# 05-LED-RED.net
KiCad netlist of a schematic drawn in Altium Designer
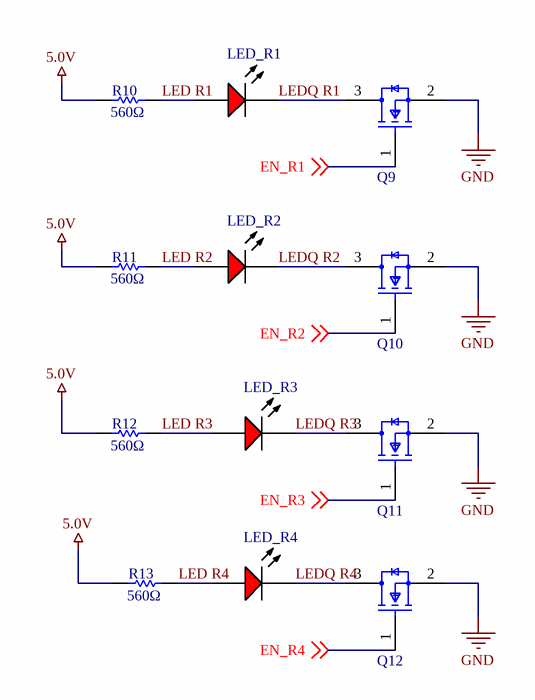
[diagram p0: 05-LED-RED.SchDoc]

(export (version "E")
  (design (tool "Eeschema 10.0.6"))
  (components
    (comp (ref "LED_R1")
      (value "SML-LX1206IC-TR")
      (footprint "LUMX-SML-LX1206IC_V")
      (description "LED Red, 65 mW, -40 to 85 degC, 2-Pin SMD, RoHS, Tape and Reel")
      (fields (field (name "MANUFACTURER") "Lumex"))
      (libsource (lib "Altium Content Vault") (part "LED-RED-AK-2"))
    )
    (comp (ref "LED_R2")
      (value "SML-LX1206IC-TR")
      (footprint "LUMX-SML-LX1206IC_V")
      (description "LED Red, 65 mW, -40 to 85 degC, 2-Pin SMD, RoHS, Tape and Reel")
      (fields (field (name "MANUFACTURER") "Lumex"))
      (libsource (lib "Altium Content Vault") (part "LED-RED-AK-2"))
    )
    (comp (ref "LED_R3")
      (value "SML-LX1206IC-TR")
      (footprint "LUMX-SML-LX1206IC_V")
      (description "LED Red, 65 mW, -40 to 85 degC, 2-Pin SMD, RoHS, Tape and Reel")
      (fields (field (name "MANUFACTURER") "Lumex"))
      (libsource (lib "Altium Content Vault") (part "LED-RED-AK-2"))
    )
    (comp (ref "LED_R4")
      (value "SML-LX1206IC-TR")
      (footprint "LUMX-SML-LX1206IC_V")
      (description "LED Red, 65 mW, -40 to 85 degC, 2-Pin SMD, RoHS, Tape and Reel")
      (fields (field (name "MANUFACTURER") "Lumex"))
      (libsource (lib "Altium Content Vault") (part "LED-RED-AK-2"))
    )
    (comp (ref "Q9")
      (value "2N7002-7-F")
      (footprint "FP-SOT23-MFG")
      (description "MOSFET N-CH 60V 115MA SOT23-3")
      (fields (field (name "VOLTAGE") "60V"))
      (libsource (lib "Altium Content Vault") (part "3b9c635fedb024a5347a57b145af9cc"))
    )
    (comp (ref "Q10")
      (value "2N7002-7-F")
      (footprint "FP-SOT23-MFG")
      (description "MOSFET N-CH 60V 115MA SOT23-3")
      (fields (field (name "VOLTAGE") "60V"))
      (libsource (lib "Altium Content Vault") (part "3b9c635fedb024a5347a57b145af9cc"))
    )
    (comp (ref "Q11")
      (value "2N7002-7-F")
      (footprint "FP-SOT23-MFG")
      (description "MOSFET N-CH 60V 115MA SOT23-3")
      (fields (field (name "VOLTAGE") "60V"))
      (libsource (lib "Altium Content Vault") (part "3b9c635fedb024a5347a57b145af9cc"))
    )
    (comp (ref "Q12")
      (value "2N7002-7-F")
      (footprint "FP-SOT23-MFG")
      (description "MOSFET N-CH 60V 115MA SOT23-3")
      (fields (field (name "VOLTAGE") "60V"))
      (libsource (lib "Altium Content Vault") (part "3b9c635fedb024a5347a57b145af9cc"))
    )
    (comp (ref "R10")
      (value "560Ω")
      (footprint "RESC3216X70X50LL05T20")
      (fields (field (name "PART NUMBER") "ERJ8ENF5600V") (field (name "MANUFACTURER") "Panasonic"))
      (libsource (lib "Altium Content Vault") (part "RES"))
    )
    (comp (ref "R11")
      (value "560Ω")
      (footprint "RESC3216X70X50LL05T20")
      (fields (field (name "PART NUMBER") "ERJ8ENF5600V") (field (name "MANUFACTURER") "Panasonic"))
      (libsource (lib "Altium Content Vault") (part "RES"))
    )
    (comp (ref "R12")
      (value "560Ω")
      (footprint "RESC3216X70X50LL05T20")
      (fields (field (name "PART NUMBER") "ERJ8ENF5600V") (field (name "MANUFACTURER") "Panasonic"))
      (libsource (lib "Altium Content Vault") (part "RES"))
    )
    (comp (ref "R13")
      (value "560Ω")
      (footprint "RESC3216X70X50LL05T20")
      (fields (field (name "PART NUMBER") "ERJ8ENF5600V") (field (name "MANUFACTURER") "Panasonic"))
      (libsource (lib "Altium Content Vault") (part "RES"))
    )
  )
  (nets
    (net (code "1") (name "/LED R1") (class "Default")
      (node (ref "LED_R1") (pin "1") (pinfunction "A_1") (pintype "passive"))
      (node (ref "R10") (pin "2") (pinfunction "2_2") (pintype "passive"))
    )
    (net (code "2") (name "/LED R2") (class "Default")
      (node (ref "LED_R2") (pin "1") (pinfunction "A_1") (pintype "passive"))
      (node (ref "R11") (pin "2") (pinfunction "2_2") (pintype "passive"))
    )
    (net (code "3") (name "/LED R3") (class "Default")
      (node (ref "LED_R3") (pin "1") (pinfunction "A_1") (pintype "passive"))
      (node (ref "R12") (pin "2") (pinfunction "2_2") (pintype "passive"))
    )
    (net (code "4") (name "/LED R4") (class "Default")
      (node (ref "LED_R4") (pin "1") (pinfunction "A_1") (pintype "passive"))
      (node (ref "R13") (pin "2") (pinfunction "2_2") (pintype "passive"))
    )
    (net (code "5") (name "/LEDQ R1") (class "Default")
      (node (ref "LED_R1") (pin "2") (pinfunction "K_2") (pintype "passive"))
      (node (ref "Q9") (pin "3") (pinfunction "D_3") (pintype "passive"))
    )
    (net (code "6") (name "/LEDQ R2") (class "Default")
      (node (ref "LED_R2") (pin "2") (pinfunction "K_2") (pintype "passive"))
      (node (ref "Q10") (pin "3") (pinfunction "D_3") (pintype "passive"))
    )
    (net (code "7") (name "/LEDQ R3") (class "Default")
      (node (ref "LED_R3") (pin "2") (pinfunction "K_2") (pintype "passive"))
      (node (ref "Q11") (pin "3") (pinfunction "D_3") (pintype "passive"))
    )
    (net (code "8") (name "/LEDQ R4") (class "Default")
      (node (ref "LED_R4") (pin "2") (pinfunction "K_2") (pintype "passive"))
      (node (ref "Q12") (pin "3") (pinfunction "D_3") (pintype "passive"))
    )
    (net (code "9") (name "5.0V") (class "Default")
      (node (ref "R10") (pin "1") (pinfunction "1_1") (pintype "passive"))
      (node (ref "R11") (pin "1") (pinfunction "1_1") (pintype "passive"))
      (node (ref "R12") (pin "1") (pinfunction "1_1") (pintype "passive"))
      (node (ref "R13") (pin "1") (pinfunction "1_1") (pintype "passive"))
    )
    (net (code "10") (name "EN_R1") (class "Default")
      (node (ref "Q9") (pin "1") (pinfunction "G_1") (pintype "passive"))
    )
    (net (code "11") (name "EN_R2") (class "Default")
      (node (ref "Q10") (pin "1") (pinfunction "G_1") (pintype "passive"))
    )
    (net (code "12") (name "EN_R3") (class "Default")
      (node (ref "Q11") (pin "1") (pinfunction "G_1") (pintype "passive"))
    )
    (net (code "13") (name "EN_R4") (class "Default")
      (node (ref "Q12") (pin "1") (pinfunction "G_1") (pintype "passive"))
    )
    (net (code "14") (name "GND") (class "Default")
      (node (ref "Q10") (pin "2") (pinfunction "S_2") (pintype "passive"))
      (node (ref "Q11") (pin "2") (pinfunction "S_2") (pintype "passive"))
      (node (ref "Q12") (pin "2") (pinfunction "S_2") (pintype "passive"))
      (node (ref "Q9") (pin "2") (pinfunction "S_2") (pintype "passive"))
    )
  )
)
